# placa_6_0.net
KiCad netlist of a schematic drawn in EAGLE
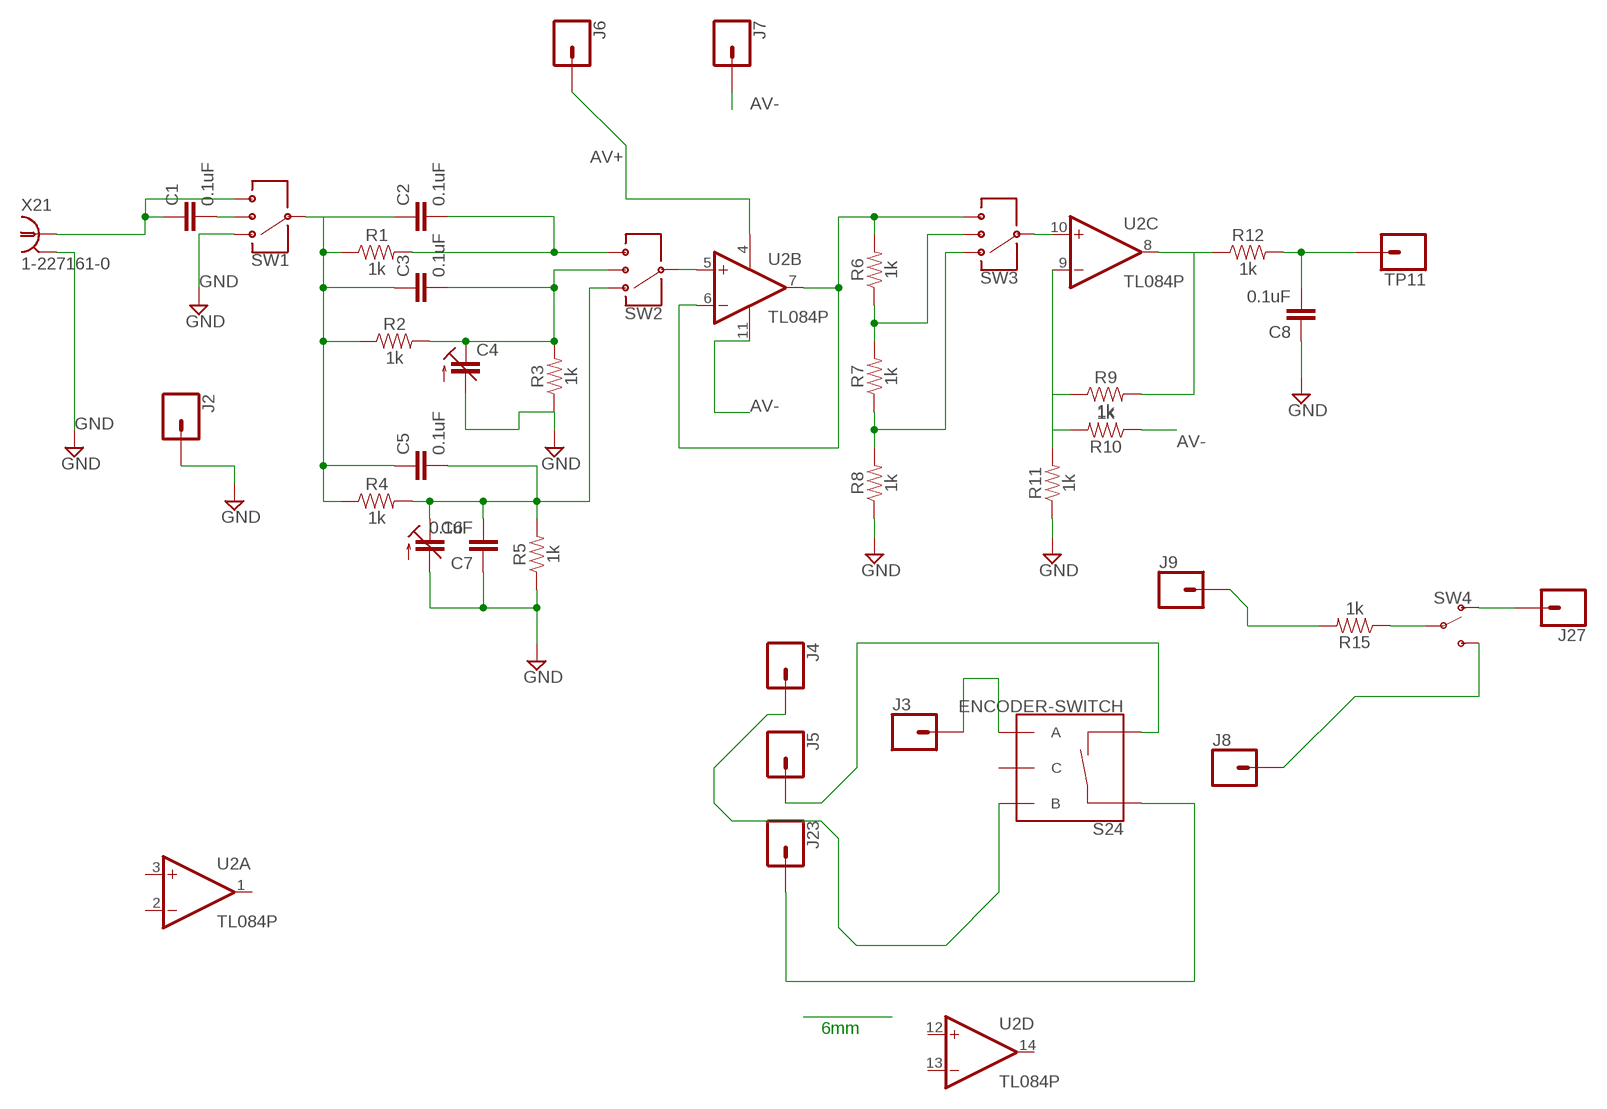
[diagram p0: schematic, sheet 1]

(export (version "E")
  (design (tool "Eeschema 10.0.6"))
  (components
    (comp (ref "C1")
      (value "0.1uF")
      (footprint "eagle-import:CAP-PTH-SMALL-KIT")
      (libsource (lib "eagle-import") (part "0.1UF-KIT-EZ-50V-20%"))
    )
    (comp (ref "C2")
      (value "0.1uF")
      (footprint "eagle-import:CAP-PTH-SMALL-KIT")
      (libsource (lib "eagle-import") (part "0.1UF-KIT-EZ-50V-20%"))
    )
    (comp (ref "C3")
      (value "0.1uF")
      (footprint "eagle-import:CAP-PTH-SMALL-KIT")
      (libsource (lib "eagle-import") (part "0.1UF-KIT-EZ-50V-20%"))
    )
    (comp (ref "C4")
      (value "C-TRIMM3050.504")
      (footprint "eagle-import:CTRIM3050.504")
      (libsource (lib "eagle-import") (part "C-TRIMM3050.504"))
    )
    (comp (ref "C5")
      (value "0.1uF")
      (footprint "eagle-import:CAP-PTH-SMALL-KIT")
      (libsource (lib "eagle-import") (part "0.1UF-KIT-EZ-50V-20%"))
    )
    (comp (ref "C6")
      (value "C-TRIMM3050.504")
      (footprint "eagle-import:CTRIM3050.504")
      (libsource (lib "eagle-import") (part "C-TRIMM3050.504"))
    )
    (comp (ref "C7")
      (value "0.1uF")
      (footprint "eagle-import:CAP-PTH-SMALL-KIT")
      (libsource (lib "eagle-import") (part "0.1UF-KIT-EZ-50V-20%"))
    )
    (comp (ref "C8")
      (value "0.1uF")
      (footprint "eagle-import:CAP-PTH-SMALL-KIT")
      (libsource (lib "eagle-import") (part "0.1UF-KIT-EZ-50V-20%"))
    )
    (comp (ref "J2")
      (value "CONN_01")
      (footprint "eagle-import:1X01")
      (libsource (lib "eagle-import") (part "CONN_01"))
    )
    (comp (ref "J3")
      (value "CONN_01")
      (footprint "eagle-import:1X01")
      (libsource (lib "eagle-import") (part "CONN_01"))
    )
    (comp (ref "J4")
      (value "CONN_01")
      (footprint "eagle-import:1X01")
      (libsource (lib "eagle-import") (part "CONN_01"))
    )
    (comp (ref "J5")
      (value "CONN_01")
      (footprint "eagle-import:1X01")
      (libsource (lib "eagle-import") (part "CONN_01"))
    )
    (comp (ref "J6")
      (value "CONN_01")
      (footprint "eagle-import:1X01")
      (libsource (lib "eagle-import") (part "CONN_01"))
    )
    (comp (ref "J7")
      (value "CONN_01")
      (footprint "eagle-import:1X01")
      (libsource (lib "eagle-import") (part "CONN_01"))
    )
    (comp (ref "J8")
      (value "CONN_01")
      (footprint "eagle-import:1X01")
      (libsource (lib "eagle-import") (part "CONN_01"))
    )
    (comp (ref "J9")
      (value "CONN_01")
      (footprint "eagle-import:1X01")
      (libsource (lib "eagle-import") (part "CONN_01"))
    )
    (comp (ref "J23")
      (value "CONN_01")
      (footprint "eagle-import:1X01")
      (libsource (lib "eagle-import") (part "CONN_01"))
    )
    (comp (ref "J27")
      (value "CONN_01")
      (footprint "eagle-import:1X01")
      (libsource (lib "eagle-import") (part "CONN_01"))
    )
    (comp (ref "R1")
      (value "1k")
      (footprint "eagle-import:AXIAL-0.3")
      (libsource (lib "eagle-import") (part "1KOHM-HORIZ-1/4W-1%"))
    )
    (comp (ref "R2")
      (value "1k")
      (footprint "eagle-import:AXIAL-0.3")
      (libsource (lib "eagle-import") (part "1KOHM-HORIZ-1/4W-1%"))
    )
    (comp (ref "R3")
      (value "1k")
      (footprint "eagle-import:AXIAL-0.3")
      (libsource (lib "eagle-import") (part "1KOHM-HORIZ-1/4W-1%"))
    )
    (comp (ref "R4")
      (value "1k")
      (footprint "eagle-import:AXIAL-0.3")
      (libsource (lib "eagle-import") (part "1KOHM-HORIZ-1/4W-1%"))
    )
    (comp (ref "R5")
      (value "1k")
      (footprint "eagle-import:AXIAL-0.3")
      (libsource (lib "eagle-import") (part "1KOHM-HORIZ-1/4W-1%"))
    )
    (comp (ref "R6")
      (value "1k")
      (footprint "eagle-import:AXIAL-0.3")
      (libsource (lib "eagle-import") (part "1KOHM-HORIZ-1/4W-1%"))
    )
    (comp (ref "R7")
      (value "1k")
      (footprint "eagle-import:AXIAL-0.3")
      (libsource (lib "eagle-import") (part "1KOHM-HORIZ-1/4W-1%"))
    )
    (comp (ref "R8")
      (value "1k")
      (footprint "eagle-import:AXIAL-0.3")
      (libsource (lib "eagle-import") (part "1KOHM-HORIZ-1/4W-1%"))
    )
    (comp (ref "R9")
      (value "1k")
      (footprint "eagle-import:AXIAL-0.3")
      (libsource (lib "eagle-import") (part "1KOHM-HORIZ-1/4W-1%"))
    )
    (comp (ref "R10")
      (value "1k")
      (footprint "eagle-import:AXIAL-0.3")
      (libsource (lib "eagle-import") (part "1KOHM-HORIZ-1/4W-1%"))
    )
    (comp (ref "R11")
      (value "1k")
      (footprint "eagle-import:AXIAL-0.3")
      (libsource (lib "eagle-import") (part "1KOHM-HORIZ-1/4W-1%"))
    )
    (comp (ref "R12")
      (value "1k")
      (footprint "eagle-import:AXIAL-0.3")
      (libsource (lib "eagle-import") (part "1KOHM-HORIZ-1/4W-1%"))
    )
    (comp (ref "R15")
      (value "1k")
      (footprint "eagle-import:AXIAL-0.3")
      (libsource (lib "eagle-import") (part "1KOHM-HORIZ-1/4W-1%"))
    )
    (comp (ref "S24")
      (value "ENCODER-SWITCH")
      (footprint "eagle-import:ROTARY_ENC_PLAIN")
      (libsource (lib "eagle-import") (part "ENCODER-SWITCH"))
    )
    (comp (ref "SW1")
      (value "SWITCH-SP3T-SMD")
      (footprint "eagle-import:SWITCH_SP3T_SMD")
      (libsource (lib "eagle-import") (part "SWITCH-SP3T-SMD"))
    )
    (comp (ref "SW2")
      (value "SWITCH-SP3T-SMD")
      (footprint "eagle-import:SWITCH_SP3T_SMD")
      (libsource (lib "eagle-import") (part "SWITCH-SP3T-SMD"))
    )
    (comp (ref "SW3")
      (value "SWITCH-SP3T-SMD")
      (footprint "eagle-import:SWITCH_SP3T_SMD")
      (libsource (lib "eagle-import") (part "SWITCH-SP3T-SMD"))
    )
    (comp (ref "SW4")
      (value "SWITCH-SPDT-PTH-11.6X4.0MM")
      (footprint "eagle-import:SWITCH_SPDT_PTH_11.6X4.0MM")
      (libsource (lib "eagle-import") (part "SWITCH-SPDT-PTH-11.6X4.0MM"))
    )
    (comp (ref "TP11")
      (value "CONN_01")
      (footprint "eagle-import:1X01")
      (libsource (lib "eagle-import") (part "CONN_01"))
    )
    (comp (ref "U2")
      (value "TL084P")
      (footprint "eagle-import:DIL14")
      (libsource (lib "eagle-import") (part "TL084P"))
    )
    (comp (ref "X21")
      (value "1-227161-0")
      (footprint "eagle-import:AMP_227161")
      (fields (field (name "MF") "TYCO ELECTRONICS") (field (name "MPN") "1-227161"))
      (libsource (lib "eagle-import") (part "?2271611--0"))
    )
  )
  (nets
    (net (code "1") (name "/AV+") (class "Default")
      (node (ref "J6") (pin "1") (pinfunction "1_1") (pintype "passive"))
      (node (ref "U2") (pin "4") (pinfunction "V+_4") (pintype "power_in"))
    )
    (net (code "2") (name "/AV-") (class "Default")
      (node (ref "J7") (pin "1") (pinfunction "1_1") (pintype "passive"))
      (node (ref "R10") (pin "P$1") (pinfunction "1_P$1") (pintype "passive"))
      (node (ref "U2") (pin "11") (pinfunction "V-_11") (pintype "power_in"))
    )
    (net (code "3") (name "GND") (class "Default")
      (node (ref "C4") (pin "2") (pinfunction "A_2") (pintype "passive"))
      (node (ref "C6") (pin "2") (pinfunction "A_2") (pintype "passive"))
      (node (ref "C7") (pin "1") (pinfunction "1_1") (pintype "passive"))
      (node (ref "C8") (pin "1") (pinfunction "1_1") (pintype "passive"))
      (node (ref "J2") (pin "1") (pinfunction "1_1") (pintype "passive"))
      (node (ref "R11") (pin "P$1") (pinfunction "1_P$1") (pintype "passive"))
      (node (ref "R3") (pin "P$1") (pinfunction "1_P$1") (pintype "passive"))
      (node (ref "R5") (pin "P$1") (pinfunction "1_P$1") (pintype "passive"))
      (node (ref "R8") (pin "P$1") (pinfunction "1_P$1") (pintype "passive"))
      (node (ref "SW1") (pin "IO1") (pinfunction "1_IO1") (pintype "bidirectional"))
      (node (ref "X21") (pin "2") (pinfunction "2_2") (pintype "passive"))
    )
    (net (code "4") (name "Net-(C1-2)") (class "Default")
      (node (ref "C1") (pin ">NAME") (pinfunction "2_>NAME") (pintype "passive"))
      (node (ref "SW1") (pin "IO2") (pinfunction "2_IO2") (pintype "bidirectional"))
    )
    (net (code "5") (name "Net-(C2-2)") (class "Default")
      (node (ref "C2") (pin ">NAME") (pinfunction "2_>NAME") (pintype "passive"))
      (node (ref "R1") (pin "P$2") (pinfunction "2_P$2") (pintype "passive"))
      (node (ref "SW2") (pin "IO4") (pinfunction "4_IO4") (pintype "bidirectional"))
    )
    (net (code "6") (name "Net-(C3-2)") (class "Default")
      (node (ref "C3") (pin ">NAME") (pinfunction "2_>NAME") (pintype "passive"))
      (node (ref "C4") (pin "1") (pinfunction "E_1") (pintype "passive"))
      (node (ref "R2") (pin "P$2") (pinfunction "2_P$2") (pintype "passive"))
      (node (ref "R3") (pin "P$2") (pinfunction "2_P$2") (pintype "passive"))
      (node (ref "SW2") (pin "IO2") (pinfunction "2_IO2") (pintype "bidirectional"))
    )
    (net (code "7") (name "Net-(C5-2)") (class "Default")
      (node (ref "C5") (pin ">NAME") (pinfunction "2_>NAME") (pintype "passive"))
      (node (ref "C6") (pin "1") (pinfunction "E_1") (pintype "passive"))
      (node (ref "C7") (pin ">NAME") (pinfunction "2_>NAME") (pintype "passive"))
      (node (ref "R4") (pin "P$2") (pinfunction "2_P$2") (pintype "passive"))
      (node (ref "R5") (pin "P$2") (pinfunction "2_P$2") (pintype "passive"))
      (node (ref "SW2") (pin "IO1") (pinfunction "1_IO1") (pintype "bidirectional"))
    )
    (net (code "8") (name "Net-(C8-2)") (class "Default")
      (node (ref "C8") (pin ">NAME") (pinfunction "2_>NAME") (pintype "passive"))
      (node (ref "R12") (pin "P$2") (pinfunction "2_P$2") (pintype "passive"))
      (node (ref "TP11") (pin "1") (pinfunction "1_1") (pintype "passive"))
    )
    (net (code "9") (name "Net-(J3-Pad1)") (class "Default")
      (node (ref "J3") (pin "1") (pinfunction "1_1") (pintype "passive"))
      (node (ref "S24") (pin "A") (pinfunction "A_A") (pintype "bidirectional"))
    )
    (net (code "10") (name "Net-(J4-Pad1)") (class "Default")
      (node (ref "J4") (pin "1") (pinfunction "1_1") (pintype "passive"))
      (node (ref "S24") (pin "B") (pinfunction "B_B") (pintype "bidirectional"))
    )
    (net (code "11") (name "Net-(J5-Pad1)") (class "Default")
      (node (ref "J5") (pin "1") (pinfunction "1_1") (pintype "passive"))
      (node (ref "S24") (pin "SW-") (pinfunction "SW-_SW-") (pintype "bidirectional"))
    )
    (net (code "12") (name "Net-(J23-Pad1)") (class "Default")
      (node (ref "J23") (pin "1") (pinfunction "1_1") (pintype "passive"))
      (node (ref "S24") (pin "SW+") (pinfunction "SW+_SW+") (pintype "bidirectional"))
    )
    (net (code "13") (name "Net-(R1-1)") (class "Default")
      (node (ref "C2") (pin "1") (pinfunction "1_1") (pintype "passive"))
      (node (ref "C3") (pin "1") (pinfunction "1_1") (pintype "passive"))
      (node (ref "C5") (pin "1") (pinfunction "1_1") (pintype "passive"))
      (node (ref "R1") (pin "P$1") (pinfunction "1_P$1") (pintype "passive"))
      (node (ref "R2") (pin "P$1") (pinfunction "1_P$1") (pintype "passive"))
      (node (ref "R4") (pin "P$1") (pinfunction "1_P$1") (pintype "passive"))
      (node (ref "SW1") (pin "IO3") (pinfunction "3_IO3") (pintype "bidirectional"))
    )
    (net (code "14") (name "Net-(R6-1)") (class "Default")
      (node (ref "R6") (pin "P$1") (pinfunction "1_P$1") (pintype "passive"))
      (node (ref "R7") (pin "P$2") (pinfunction "2_P$2") (pintype "passive"))
      (node (ref "SW3") (pin "IO2") (pinfunction "2_IO2") (pintype "bidirectional"))
    )
    (net (code "15") (name "Net-(R6-2)") (class "Default")
      (node (ref "R6") (pin "P$2") (pinfunction "2_P$2") (pintype "passive"))
      (node (ref "SW3") (pin "IO4") (pinfunction "4_IO4") (pintype "bidirectional"))
      (node (ref "U2") (pin "6") (pinfunction "-IN_6") (pintype "input"))
      (node (ref "U2") (pin "7") (pinfunction "OUT_7") (pintype "output"))
    )
    (net (code "16") (name "Net-(R7-1)") (class "Default")
      (node (ref "R7") (pin "P$1") (pinfunction "1_P$1") (pintype "passive"))
      (node (ref "R8") (pin "P$2") (pinfunction "2_P$2") (pintype "passive"))
      (node (ref "SW3") (pin "IO1") (pinfunction "1_IO1") (pintype "bidirectional"))
    )
    (net (code "17") (name "Net-(R10-2)") (class "Default")
      (node (ref "R10") (pin "P$2") (pinfunction "2_P$2") (pintype "passive"))
      (node (ref "R11") (pin "P$2") (pinfunction "2_P$2") (pintype "passive"))
      (node (ref "R9") (pin "P$1") (pinfunction "1_P$1") (pintype "passive"))
      (node (ref "U2") (pin "9") (pinfunction "-IN_9") (pintype "input"))
    )
    (net (code "18") (name "Net-(R12-1)") (class "Default")
      (node (ref "R12") (pin "P$1") (pinfunction "1_P$1") (pintype "passive"))
      (node (ref "R9") (pin "P$2") (pinfunction "2_P$2") (pintype "passive"))
      (node (ref "U2") (pin "8") (pinfunction "OUT_8") (pintype "output"))
    )
    (net (code "19") (name "Net-(R15-1)") (class "Default")
      (node (ref "R15") (pin "P$1") (pinfunction "1_P$1") (pintype "passive"))
      (node (ref "SW4") (pin "2") (pinfunction "P_2") (pintype "passive"))
    )
    (net (code "20") (name "Net-(R15-2)") (class "Default")
      (node (ref "J9") (pin "1") (pinfunction "1_1") (pintype "passive"))
      (node (ref "R15") (pin "P$2") (pinfunction "2_P$2") (pintype "passive"))
    )
    (net (code "21") (name "Net-(SW1-4)") (class "Default")
      (node (ref "C1") (pin "1") (pinfunction "1_1") (pintype "passive"))
      (node (ref "SW1") (pin "IO4") (pinfunction "4_IO4") (pintype "bidirectional"))
      (node (ref "X21") (pin "1") (pinfunction "1_1") (pintype "passive"))
    )
    (net (code "22") (name "Net-(SW2-3)") (class "Default")
      (node (ref "SW2") (pin "IO3") (pinfunction "3_IO3") (pintype "bidirectional"))
      (node (ref "U2") (pin "5") (pinfunction "+IN_5") (pintype "input"))
    )
    (net (code "23") (name "Net-(SW3-3)") (class "Default")
      (node (ref "SW3") (pin "IO3") (pinfunction "3_IO3") (pintype "bidirectional"))
      (node (ref "U2") (pin "10") (pinfunction "+IN_10") (pintype "input"))
    )
    (net (code "24") (name "Net-(SW4-O)") (class "Default")
      (node (ref "J27") (pin "1") (pinfunction "1_1") (pintype "passive"))
      (node (ref "SW4") (pin "1") (pinfunction "O_1") (pintype "passive"))
    )
    (net (code "25") (name "Net-(SW4-S)") (class "Default")
      (node (ref "J8") (pin "1") (pinfunction "1_1") (pintype "passive"))
      (node (ref "SW4") (pin "3") (pinfunction "S_3") (pintype "passive"))
    )
    (net (code "26") (name "unconnected-(S24-PadC)") (class "Default")
      (node (ref "S24") (pin "C") (pinfunction "C_C") (pintype "bidirectional"))
    )
    (net (code "27") (name "unconnected-(U2A-+IN-Pad3)") (class "Default")
      (node (ref "U2") (pin "3") (pinfunction "+IN_3") (pintype "input"))
    )
    (net (code "28") (name "unconnected-(U2A--IN-Pad2)") (class "Default")
      (node (ref "U2") (pin "2") (pinfunction "-IN_2") (pintype "input"))
    )
    (net (code "29") (name "unconnected-(U2A-OUT-Pad1)") (class "Default")
      (node (ref "U2") (pin "1") (pinfunction "OUT_1") (pintype "output"))
    )
    (net (code "30") (name "unconnected-(U2D-+IN-Pad12)") (class "Default")
      (node (ref "U2") (pin "12") (pinfunction "+IN_12") (pintype "input"))
    )
    (net (code "31") (name "unconnected-(U2D--IN-Pad13)") (class "Default")
      (node (ref "U2") (pin "13") (pinfunction "-IN_13") (pintype "input"))
    )
    (net (code "32") (name "unconnected-(U2D-OUT-Pad14)") (class "Default")
      (node (ref "U2") (pin "14") (pinfunction "OUT_14") (pintype "output"))
    )
  )
)
